# Interface.net
KiCad netlist of a schematic drawn in Altium Designer
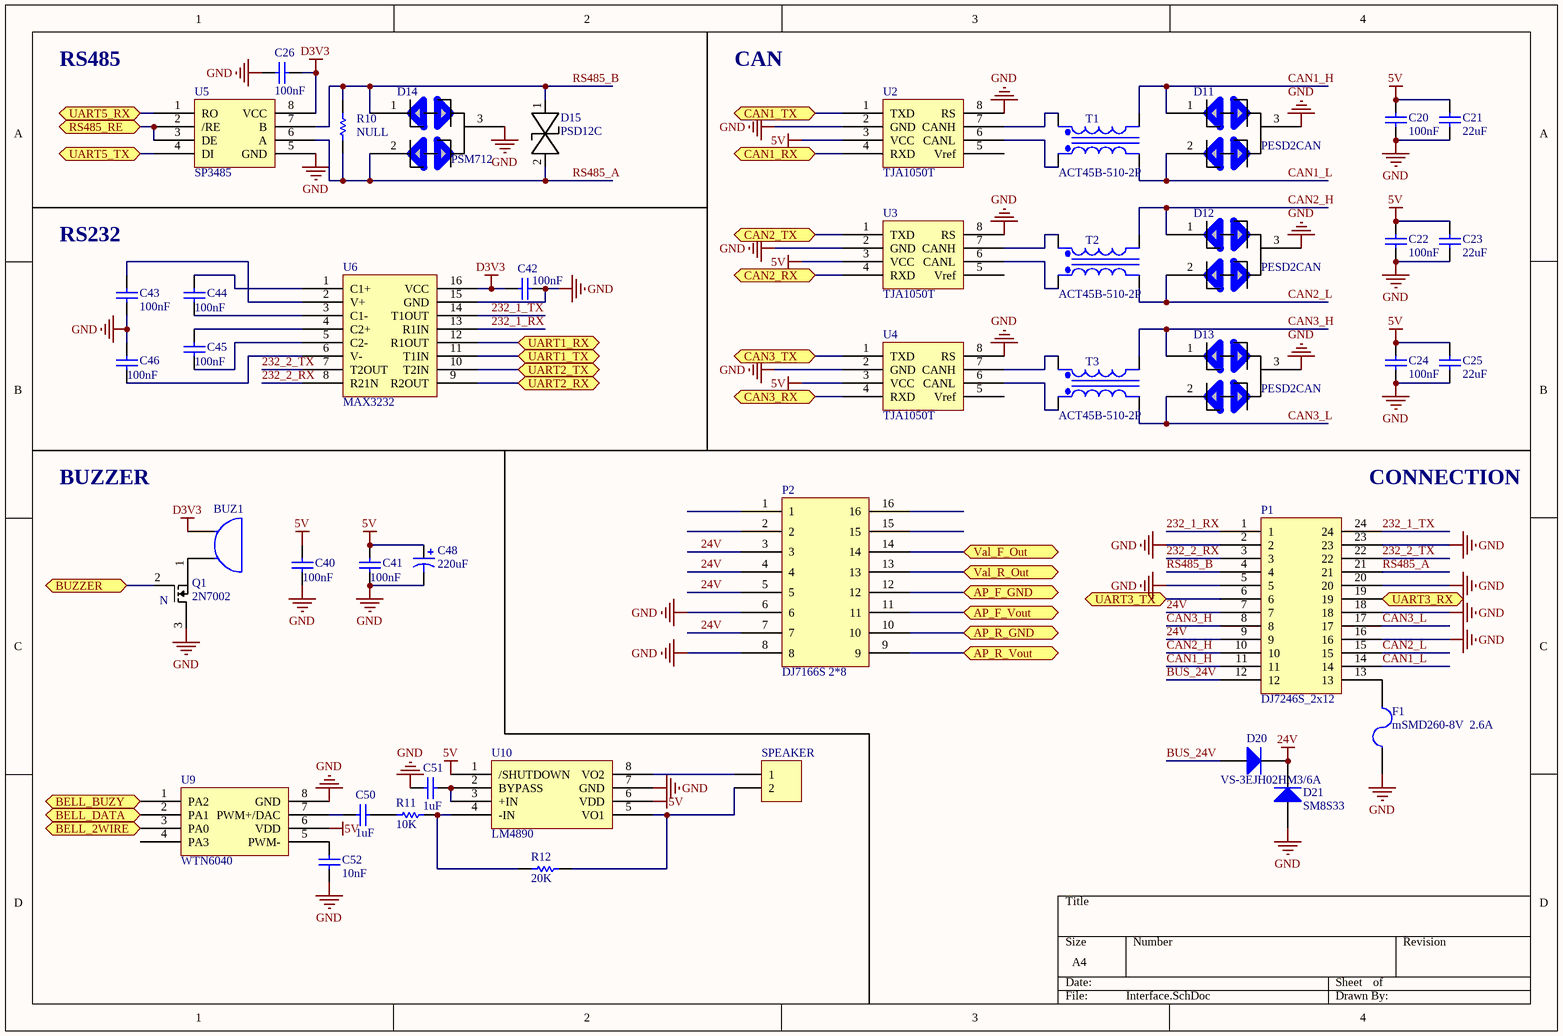
[diagram p0: Interface.SchDoc]

(export (version "E")
  (design (tool "Eeschema 10.0.6"))
  (components
    (comp (ref "BUZ1")
      (value "BUZZER")
      (footprint "BUZ0905")
      (description "Buzzer")
      (libsource (lib "杂元件库") (part "BUZZER"))
    )
    (comp (ref "C20")
      (value "100nF")
      (footprint "BinFeng:0402")
      (description "Capacitor")
      (fields (field (name "PUBLISHER") "Altium Limited"))
      (libsource (lib "Miscellaneous Devices") (part "Cap"))
    )
    (comp (ref "C21")
      (value "22uF")
      (footprint "0805")
      (description "Capacitor")
      (fields (field (name "PUBLISHER") "Altium Limited"))
      (libsource (lib "Miscellaneous Devices") (part "Cap"))
    )
    (comp (ref "C22")
      (value "100nF")
      (footprint "BinFeng:0402")
      (description "Capacitor")
      (fields (field (name "PUBLISHER") "Altium Limited"))
      (libsource (lib "Miscellaneous Devices") (part "Cap"))
    )
    (comp (ref "C23")
      (value "22uF")
      (footprint "0805")
      (description "Capacitor")
      (fields (field (name "PUBLISHER") "Altium Limited"))
      (libsource (lib "Miscellaneous Devices") (part "Cap"))
    )
    (comp (ref "C24")
      (value "100nF")
      (footprint "BinFeng:0402")
      (description "Capacitor")
      (fields (field (name "PUBLISHER") "Altium Limited"))
      (libsource (lib "Miscellaneous Devices") (part "Cap"))
    )
    (comp (ref "C25")
      (value "22uF")
      (footprint "0805")
      (description "Capacitor")
      (fields (field (name "PUBLISHER") "Altium Limited"))
      (libsource (lib "Miscellaneous Devices") (part "Cap"))
    )
    (comp (ref "C26")
      (value "100nF")
      (footprint "BinFeng:0603")
      (description "Capacitor")
      (fields (field (name "PUBLISHER") "Altium Limited"))
      (libsource (lib "Miscellaneous Devices") (part "Cap"))
    )
    (comp (ref "C40")
      (value "100nF")
      (footprint "BinFeng:0402")
      (description "Capacitor")
      (fields (field (name "PUBLISHER") "Altium Limited"))
      (libsource (lib "Miscellaneous Devices") (part "Cap"))
    )
    (comp (ref "C41")
      (value "100nF")
      (footprint "BinFeng:0402")
      (description "Capacitor")
      (fields (field (name "PUBLISHER") "Altium Limited"))
      (libsource (lib "Miscellaneous Devices") (part "Cap"))
    )
    (comp (ref "C42")
      (value "100nF")
      (footprint "BinFeng:0402")
      (description "Capacitor")
      (fields (field (name "PUBLISHER") "Altium Limited"))
      (libsource (lib "Miscellaneous Devices") (part "Cap"))
    )
    (comp (ref "C43")
      (value "100nF")
      (footprint "BinFeng:0402")
      (description "Capacitor")
      (fields (field (name "PUBLISHER") "Altium Limited"))
      (libsource (lib "Miscellaneous Devices") (part "Cap"))
    )
    (comp (ref "C44")
      (value "100nF")
      (footprint "BinFeng:0402")
      (description "Capacitor")
      (fields (field (name "PUBLISHER") "Altium Limited"))
      (libsource (lib "Miscellaneous Devices") (part "Cap"))
    )
    (comp (ref "C45")
      (value "100nF")
      (footprint "BinFeng:0402")
      (description "Capacitor")
      (fields (field (name "PUBLISHER") "Altium Limited"))
      (libsource (lib "Miscellaneous Devices") (part "Cap"))
    )
    (comp (ref "C46")
      (value "100nF")
      (footprint "BinFeng:0402")
      (description "Capacitor")
      (fields (field (name "PUBLISHER") "Altium Limited"))
      (libsource (lib "Miscellaneous Devices") (part "Cap"))
    )
    (comp (ref "C48")
      (value "220uF")
      (footprint "cap_pol_8*10.2")
      (description "Polarized Capacitor (Radial)")
      (fields (field (name "PUBLISHER") "Altium Limited"))
      (libsource (lib "Miscellaneous Devices") (part "Cap Pol1"))
    )
    (comp (ref "C50")
      (value "1uF")
      (footprint "BinFeng:0402")
      (description "Capacitor")
      (fields (field (name "PUBLISHER") "Altium Limited"))
      (libsource (lib "Miscellaneous Devices") (part "Cap"))
    )
    (comp (ref "C51")
      (value "1uF")
      (footprint "BinFeng:0402")
      (description "Capacitor")
      (fields (field (name "PUBLISHER") "Altium Limited"))
      (libsource (lib "Miscellaneous Devices") (part "Cap"))
    )
    (comp (ref "C52")
      (value "10nF")
      (footprint "BinFeng:0402")
      (description "Capacitor")
      (fields (field (name "PUBLISHER") "Altium Limited"))
      (libsource (lib "Miscellaneous Devices") (part "Cap"))
    )
    (comp (ref "D11")
      (value "PESD2CAN")
      (footprint "SOT23")
      (libsource (lib "BinFeng_Connectors") (part "PESD1CAN"))
    )
    (comp (ref "D12")
      (value "PESD2CAN")
      (footprint "SOT23")
      (libsource (lib "BinFeng_Connectors") (part "PESD1CAN"))
    )
    (comp (ref "D13")
      (value "PESD2CAN")
      (footprint "SOT23")
      (libsource (lib "BinFeng_Connectors") (part "PESD1CAN"))
    )
    (comp (ref "D14")
      (value "PSM712")
      (footprint "SOT23")
      (libsource (lib "BinFeng_Connectors") (part "PESD1CAN"))
    )
    (comp (ref "D15") (value "PSD12C") (footprint "SOD323") (libsource (lib "BinFeng_IC") (part "PSD12C")))
    (comp (ref "D20")
      (value "VS-3EJH02HM3/6A")
      (footprint "B290")
      (description "1 Amp General Purpose Rectifier")
      (fields (field (name "PUBLISHER") "Altium Limited"))
      (libsource (lib "Miscellaneous Devices") (part "Diode 1N4007"))
    )
    (comp (ref "D21")
      (value "SM8S33")
      (footprint "SM8S")
      (description "1 Amp General Purpose Rectifier")
      (fields (field (name "PUBLISHER") "Altium Limited"))
      (libsource (lib "Miscellaneous Devices") (part "Diode 1N4007"))
    )
    (comp (ref "F1")
      (value "mSMD260-8V  2.6A")
      (footprint "1812")
      (description "Fuse")
      (fields (field (name "PUBLISHER") "Altium Limited"))
      (libsource (lib "Miscellaneous Devices") (part "Fuse 2"))
    )
    (comp (ref "P1")
      (value "DJ7246S_2x12")
      (footprint "DJ7246S_2*12")
      (libsource (lib "BinFeng_IC") (part "DJ7246S-0.7-10AW"))
    )
    (comp (ref "P2")
      (value "DJ7166S 2*8")
      (footprint "hg:DJ7161S_0.7_10AW")
      (libsource (lib "hg") (part "DJ7166S"))
    )
    (comp (ref "Q1") (value "2N7002") (footprint "2N7002") (libsource (lib "seeder") (part "N-MOSFET")))
    (comp (ref "R10")
      (value "NULL")
      (footprint "BinFeng:0603")
      (description "Resistor")
      (fields (field (name "PUBLISHER") "Altium Limited"))
      (libsource (lib "Miscellaneous Devices") (part "Res1"))
    )
    (comp (ref "R11")
      (value "10K")
      (footprint "BinFeng:0402")
      (description "Resistor")
      (fields (field (name "PUBLISHER") "Altium Limited"))
      (libsource (lib "Miscellaneous Devices") (part "Res1"))
    )
    (comp (ref "R12")
      (value "20K")
      (footprint "BinFeng:0402")
      (description "Resistor")
      (fields (field (name "PUBLISHER") "Altium Limited"))
      (libsource (lib "Miscellaneous Devices") (part "Res1"))
    )
    (comp (ref "SPEAKER")
      (value "XH2.54-2PIN")
      (footprint "HDR1X2")
      (description "Header, 2-Pin")
      (fields (field (name "PUBLISHER") "Altium Limited"))
      (libsource (lib "Miscellaneous Connectors") (part "Header 2"))
    )
    (comp (ref "T1")
      (value "ACT45B-510-2P")
      (footprint "ACT45B-510-2P")
      (description "Transformer (Equivalent Circuit Model)")
      (fields (field (name "PUBLISHER") "Altium Limited"))
      (libsource (lib "Miscellaneous Devices") (part "Trans Eq"))
    )
    (comp (ref "T2")
      (value "ACT45B-510-2P")
      (footprint "ACT45B-510-2P")
      (description "Transformer (Equivalent Circuit Model)")
      (fields (field (name "PUBLISHER") "Altium Limited"))
      (libsource (lib "Miscellaneous Devices") (part "Trans Eq"))
    )
    (comp (ref "T3")
      (value "ACT45B-510-2P")
      (footprint "ACT45B-510-2P")
      (description "Transformer (Equivalent Circuit Model)")
      (fields (field (name "PUBLISHER") "Altium Limited"))
      (libsource (lib "Miscellaneous Devices") (part "Trans Eq"))
    )
    (comp (ref "U2")
      (value "TJA1050T")
      (footprint "SO8")
      (description "CAN Tranceiver")
      (libsource (lib "BinFeng_IC") (part "TJA1050T"))
    )
    (comp (ref "U3")
      (value "TJA1050T")
      (footprint "SO8")
      (description "CAN Tranceiver")
      (libsource (lib "BinFeng_IC") (part "TJA1050T"))
    )
    (comp (ref "U4")
      (value "TJA1050T")
      (footprint "SO8")
      (description "CAN Tranceiver")
      (libsource (lib "BinFeng_IC") (part "TJA1050T"))
    )
    (comp (ref "U5") (value "SP3485") (footprint "SO-8N") (libsource (lib "BinFeng_IC") (part "SP3485")))
    (comp (ref "U6") (value "MAX3232") (footprint "SO16") (libsource (lib "MAX3232") (part "MAX3232")))
    (comp (ref "U9") (value "WTN6040") (footprint "SO8") (libsource (lib "Schlib3") (part "WTN6040")))
    (comp (ref "U10") (value "LM4890") (footprint "MSOP8") (libsource (lib "BinFeng_IC") (part "LM4890")))
  )
  (nets
    (net (code "1") (name "/232_1_RX") (class "Default")
      (node (ref "P1") (pin "1") (pinfunction "1_1") (pintype "passive"))
      (node (ref "U6") (pin "13") (pinfunction "R1IN_13") (pintype "passive"))
    )
    (net (code "2") (name "/232_1_TX") (class "Default")
      (node (ref "P1") (pin "24") (pinfunction "24_24") (pintype "passive"))
      (node (ref "U6") (pin "14") (pinfunction "T1OUT_14") (pintype "passive"))
    )
    (net (code "3") (name "/232_2_RX") (class "Default")
      (node (ref "P1") (pin "3") (pinfunction "3_3") (pintype "passive"))
      (node (ref "U6") (pin "8") (pinfunction "R21N_8") (pintype "passive"))
    )
    (net (code "4") (name "/232_2_TX") (class "Default")
      (node (ref "P1") (pin "22") (pinfunction "22_22") (pintype "passive"))
      (node (ref "U6") (pin "7") (pinfunction "T2OUT_7") (pintype "passive"))
    )
    (net (code "5") (name "/AP_F_GND") (class "Default")
      (node (ref "P2") (pin "12") (pinfunction "12_12") (pintype "passive"))
    )
    (net (code "6") (name "/AP_F_Vout") (class "Default")
      (node (ref "P2") (pin "11") (pinfunction "11_11") (pintype "passive"))
    )
    (net (code "7") (name "/AP_R_GND") (class "Default")
      (node (ref "P2") (pin "10") (pinfunction "10_10") (pintype "passive"))
    )
    (net (code "8") (name "/AP_R_Vout") (class "Default")
      (node (ref "P2") (pin "9") (pinfunction "9_9") (pintype "passive"))
    )
    (net (code "9") (name "/BELL_2WIRE") (class "Default")
      (node (ref "U9") (pin "3") (pinfunction "PA0_3") (pintype "passive"))
    )
    (net (code "10") (name "/BELL_BUZY") (class "Default")
      (node (ref "U9") (pin "1") (pinfunction "PA2_1") (pintype "passive"))
    )
    (net (code "11") (name "/BELL_DATA") (class "Default")
      (node (ref "U9") (pin "2") (pinfunction "PA1_2") (pintype "passive"))
    )
    (net (code "12") (name "/BUS_24V") (class "Default")
      (node (ref "D20") (pin "1") (pinfunction "A_1") (pintype "passive"))
      (node (ref "P1") (pin "12") (pinfunction "12_12") (pintype "passive"))
    )
    (net (code "13") (name "/BUZZER") (class "Default")
      (node (ref "Q1") (pin "2") (pinfunction "G_2") (pintype "passive"))
    )
    (net (code "14") (name "/CAN1_H") (class "Default")
      (node (ref "D11") (pin "1") (pinfunction "11_1") (pintype "passive"))
      (node (ref "P1") (pin "11") (pinfunction "11_11") (pintype "passive"))
      (node (ref "T1") (pin "4") (pinfunction "Sec-_4") (pintype "passive"))
    )
    (net (code "15") (name "/CAN1_L") (class "Default")
      (node (ref "D11") (pin "2") (pinfunction "12_2") (pintype "passive"))
      (node (ref "P1") (pin "14") (pinfunction "14_14") (pintype "passive"))
      (node (ref "T1") (pin "2") (pinfunction "Pri-_2") (pintype "passive"))
    )
    (net (code "16") (name "/CAN1_RX") (class "Default")
      (node (ref "U2") (pin "4") (pinfunction "RXD_4") (pintype "passive"))
    )
    (net (code "17") (name "/CAN1_TX") (class "Default")
      (node (ref "U2") (pin "1") (pinfunction "TXD_1") (pintype "passive"))
    )
    (net (code "18") (name "/CAN2_H") (class "Default")
      (node (ref "D12") (pin "1") (pinfunction "11_1") (pintype "passive"))
      (node (ref "P1") (pin "10") (pinfunction "10_10") (pintype "passive"))
      (node (ref "T2") (pin "4") (pinfunction "Sec-_4") (pintype "passive"))
    )
    (net (code "19") (name "/CAN2_L") (class "Default")
      (node (ref "D12") (pin "2") (pinfunction "12_2") (pintype "passive"))
      (node (ref "P1") (pin "15") (pinfunction "15_15") (pintype "passive"))
      (node (ref "T2") (pin "2") (pinfunction "Pri-_2") (pintype "passive"))
    )
    (net (code "20") (name "/CAN2_RX") (class "Default")
      (node (ref "U3") (pin "4") (pinfunction "RXD_4") (pintype "passive"))
    )
    (net (code "21") (name "/CAN2_TX") (class "Default")
      (node (ref "U3") (pin "1") (pinfunction "TXD_1") (pintype "passive"))
    )
    (net (code "22") (name "/CAN3_H") (class "Default")
      (node (ref "D13") (pin "1") (pinfunction "11_1") (pintype "passive"))
      (node (ref "P1") (pin "8") (pinfunction "8_8") (pintype "passive"))
      (node (ref "T3") (pin "4") (pinfunction "Sec-_4") (pintype "passive"))
    )
    (net (code "23") (name "/CAN3_L") (class "Default")
      (node (ref "D13") (pin "2") (pinfunction "12_2") (pintype "passive"))
      (node (ref "P1") (pin "17") (pinfunction "17_17") (pintype "passive"))
      (node (ref "T3") (pin "2") (pinfunction "Pri-_2") (pintype "passive"))
    )
    (net (code "24") (name "/CAN3_RX") (class "Default")
      (node (ref "U4") (pin "4") (pinfunction "RXD_4") (pintype "passive"))
    )
    (net (code "25") (name "/CAN3_TX") (class "Default")
      (node (ref "U4") (pin "1") (pinfunction "TXD_1") (pintype "passive"))
    )
    (net (code "26") (name "/RS485_A") (class "Default")
      (node (ref "D14") (pin "2") (pinfunction "12_2") (pintype "passive"))
      (node (ref "D15") (pin "2") (pinfunction "2_2") (pintype "passive"))
      (node (ref "P1") (pin "21") (pinfunction "21_21") (pintype "passive"))
      (node (ref "R10") (pin "2") (pinfunction "2_2") (pintype "passive"))
      (node (ref "U5") (pin "6") (pinfunction "A_6") (pintype "passive"))
    )
    (net (code "27") (name "/RS485_B") (class "Default")
      (node (ref "D14") (pin "1") (pinfunction "11_1") (pintype "passive"))
      (node (ref "D15") (pin "1") (pinfunction "1_1") (pintype "passive"))
      (node (ref "P1") (pin "4") (pinfunction "4_4") (pintype "passive"))
      (node (ref "R10") (pin "1") (pinfunction "1_1") (pintype "passive"))
      (node (ref "U5") (pin "7") (pinfunction "B_7") (pintype "passive"))
    )
    (net (code "28") (name "/RS485_RE") (class "Default")
      (node (ref "U5") (pin "2") (pinfunction "/RE_2") (pintype "passive"))
      (node (ref "U5") (pin "3") (pinfunction "DE_3") (pintype "passive"))
    )
    (net (code "29") (name "/UART1_RX") (class "Default")
      (node (ref "U6") (pin "12") (pinfunction "R1OUT_12") (pintype "passive"))
    )
    (net (code "30") (name "/UART1_TX") (class "Default")
      (node (ref "U6") (pin "11") (pinfunction "T1IN_11") (pintype "passive"))
    )
    (net (code "31") (name "/UART2_RX") (class "Default")
      (node (ref "U6") (pin "9") (pinfunction "R2OUT_9") (pintype "passive"))
    )
    (net (code "32") (name "/UART2_TX") (class "Default")
      (node (ref "U6") (pin "10") (pinfunction "T2IN_10") (pintype "passive"))
    )
    (net (code "33") (name "/UART3_RX") (class "Default")
      (node (ref "P1") (pin "19") (pinfunction "19_19") (pintype "passive"))
    )
    (net (code "34") (name "/UART3_TX") (class "Default")
      (node (ref "P1") (pin "6") (pinfunction "6_6") (pintype "passive"))
    )
    (net (code "35") (name "/UART5_RX") (class "Default")
      (node (ref "U5") (pin "1") (pinfunction "RO_1") (pintype "passive"))
    )
    (net (code "36") (name "/UART5_TX") (class "Default")
      (node (ref "U5") (pin "4") (pinfunction "DI_4") (pintype "passive"))
    )
    (net (code "37") (name "/Val_F_Out") (class "Default")
      (node (ref "P2") (pin "14") (pinfunction "14_14") (pintype "passive"))
    )
    (net (code "38") (name "/Val_R_Out") (class "Default")
      (node (ref "P2") (pin "13") (pinfunction "13_13") (pintype "passive"))
    )
    (net (code "39") (name "5V") (class "Default")
      (node (ref "C20") (pin "2") (pinfunction "2_2") (pintype "passive"))
      (node (ref "C21") (pin "2") (pinfunction "2_2") (pintype "passive"))
      (node (ref "C22") (pin "2") (pinfunction "2_2") (pintype "passive"))
      (node (ref "C23") (pin "2") (pinfunction "2_2") (pintype "passive"))
      (node (ref "C24") (pin "2") (pinfunction "2_2") (pintype "passive"))
      (node (ref "C25") (pin "2") (pinfunction "2_2") (pintype "passive"))
      (node (ref "C40") (pin "2") (pinfunction "2_2") (pintype "passive"))
      (node (ref "C41") (pin "2") (pinfunction "2_2") (pintype "passive"))
      (node (ref "C48") (pin "1") (pinfunction "1_1") (pintype "passive"))
      (node (ref "U10") (pin "1") (pinfunction "/SHUTDOWN_1") (pintype "passive"))
      (node (ref "U10") (pin "6") (pinfunction "VDD_6") (pintype "passive"))
      (node (ref "U2") (pin "3") (pinfunction "VCC_3") (pintype "passive"))
      (node (ref "U3") (pin "3") (pinfunction "VCC_3") (pintype "passive"))
      (node (ref "U4") (pin "3") (pinfunction "VCC_3") (pintype "passive"))
      (node (ref "U9") (pin "6") (pinfunction "VDD_6") (pintype "power_in"))
    )
    (net (code "40") (name "24V") (class "Default")
      (node (ref "D20") (pin "2") (pinfunction "K_2") (pintype "passive"))
      (node (ref "D21") (pin "2") (pinfunction "K_2") (pintype "passive"))
      (node (ref "P1") (pin "7") (pinfunction "7_7") (pintype "passive"))
      (node (ref "P1") (pin "9") (pinfunction "9_9") (pintype "passive"))
      (node (ref "P2") (pin "3") (pinfunction "3_3") (pintype "passive"))
      (node (ref "P2") (pin "4") (pinfunction "4_4") (pintype "passive"))
      (node (ref "P2") (pin "5") (pinfunction "5_5") (pintype "passive"))
      (node (ref "P2") (pin "7") (pinfunction "7_7") (pintype "passive"))
    )
    (net (code "41") (name "D3V3") (class "Default")
      (node (ref "BUZ1") (pin "1") (pinfunction "A_1") (pintype "passive"))
      (node (ref "C26") (pin "2") (pinfunction "2_2") (pintype "passive"))
      (node (ref "C42") (pin "2") (pinfunction "2_2") (pintype "passive"))
      (node (ref "U5") (pin "8") (pinfunction "VCC_8") (pintype "passive"))
      (node (ref "U6") (pin "16") (pinfunction "VCC_16") (pintype "passive"))
    )
    (net (code "42") (name "GND") (class "Default")
      (node (ref "C20") (pin "1") (pinfunction "1_1") (pintype "passive"))
      (node (ref "C21") (pin "1") (pinfunction "1_1") (pintype "passive"))
      (node (ref "C22") (pin "1") (pinfunction "1_1") (pintype "passive"))
      (node (ref "C23") (pin "1") (pinfunction "1_1") (pintype "passive"))
      (node (ref "C24") (pin "1") (pinfunction "1_1") (pintype "passive"))
      (node (ref "C25") (pin "1") (pinfunction "1_1") (pintype "passive"))
      (node (ref "C26") (pin "1") (pinfunction "1_1") (pintype "passive"))
      (node (ref "C40") (pin "1") (pinfunction "1_1") (pintype "passive"))
      (node (ref "C41") (pin "1") (pinfunction "1_1") (pintype "passive"))
      (node (ref "C42") (pin "1") (pinfunction "1_1") (pintype "passive"))
      (node (ref "C43") (pin "2") (pinfunction "2_2") (pintype "passive"))
      (node (ref "C46") (pin "2") (pinfunction "2_2") (pintype "passive"))
      (node (ref "C48") (pin "2") (pinfunction "2_2") (pintype "passive"))
      (node (ref "C51") (pin "2") (pinfunction "2_2") (pintype "passive"))
      (node (ref "C52") (pin "2") (pinfunction "2_2") (pintype "passive"))
      (node (ref "D11") (pin "3") (pinfunction "13_3") (pintype "passive"))
      (node (ref "D12") (pin "3") (pinfunction "13_3") (pintype "passive"))
      (node (ref "D13") (pin "3") (pinfunction "13_3") (pintype "passive"))
      (node (ref "D14") (pin "3") (pinfunction "13_3") (pintype "passive"))
      (node (ref "D21") (pin "1") (pinfunction "A_1") (pintype "passive"))
      (node (ref "F1") (pin "2") (pinfunction "2_2") (pintype "passive"))
      (node (ref "P1") (pin "16") (pinfunction "16_16") (pintype "passive"))
      (node (ref "P1") (pin "18") (pinfunction "18_18") (pintype "passive"))
      (node (ref "P1") (pin "2") (pinfunction "2_2") (pintype "passive"))
      (node (ref "P1") (pin "20") (pinfunction "20_20") (pintype "passive"))
      (node (ref "P1") (pin "23") (pinfunction "23_23") (pintype "passive"))
      (node (ref "P1") (pin "5") (pinfunction "5_5") (pintype "passive"))
      (node (ref "P2") (pin "6") (pinfunction "6_6") (pintype "passive"))
      (node (ref "P2") (pin "8") (pinfunction "8_8") (pintype "passive"))
      (node (ref "Q1") (pin "3") (pinfunction "S_3") (pintype "passive"))
      (node (ref "U10") (pin "7") (pinfunction "GND_7") (pintype "passive"))
      (node (ref "U2") (pin "2") (pinfunction "GND_2") (pintype "passive"))
      (node (ref "U2") (pin "8") (pinfunction "RS_8") (pintype "passive"))
      (node (ref "U3") (pin "2") (pinfunction "GND_2") (pintype "passive"))
      (node (ref "U3") (pin "8") (pinfunction "RS_8") (pintype "passive"))
      (node (ref "U4") (pin "2") (pinfunction "GND_2") (pintype "passive"))
      (node (ref "U4") (pin "8") (pinfunction "RS_8") (pintype "passive"))
      (node (ref "U5") (pin "5") (pinfunction "GND_5") (pintype "passive"))
      (node (ref "U6") (pin "15") (pinfunction "GND_15") (pintype "passive"))
      (node (ref "U9") (pin "8") (pinfunction "GND_8") (pintype "power_in"))
    )
    (net (code "43") (name "Net-(BUZ1-B)") (class "Default")
      (node (ref "BUZ1") (pin "2") (pinfunction "B_2") (pintype "passive"))
      (node (ref "Q1") (pin "1") (pinfunction "D_1") (pintype "passive"))
    )
    (net (code "44") (name "Net-(C50-Pad1)") (class "Default")
      (node (ref "C50") (pin "1") (pinfunction "1_1") (pintype "passive"))
      (node (ref "R11") (pin "1") (pinfunction "1_1") (pintype "passive"))
    )
    (net (code "45") (name "Net-(F1-Pad1)") (class "Default")
      (node (ref "F1") (pin "1") (pinfunction "1_1") (pintype "passive"))
      (node (ref "P1") (pin "13") (pinfunction "13_13") (pintype "passive"))
    )
    (net (code "46") (name "Net-(T1-Pri+)") (class "Default")
      (node (ref "T1") (pin "1") (pinfunction "Pri+_1") (pintype "passive"))
      (node (ref "U2") (pin "6") (pinfunction "CANL_6") (pintype "passive"))
    )
    (net (code "47") (name "Net-(T1-Sec+)") (class "Default")
      (node (ref "T1") (pin "3") (pinfunction "Sec+_3") (pintype "passive"))
      (node (ref "U2") (pin "7") (pinfunction "CANH_7") (pintype "passive"))
    )
    (net (code "48") (name "Net-(T2-Pri+)") (class "Default")
      (node (ref "T2") (pin "1") (pinfunction "Pri+_1") (pintype "passive"))
      (node (ref "U3") (pin "6") (pinfunction "CANL_6") (pintype "passive"))
    )
    (net (code "49") (name "Net-(T2-Sec+)") (class "Default")
      (node (ref "T2") (pin "3") (pinfunction "Sec+_3") (pintype "passive"))
      (node (ref "U3") (pin "7") (pinfunction "CANH_7") (pintype "passive"))
    )
    (net (code "50") (name "Net-(T3-Pri+)") (class "Default")
      (node (ref "T3") (pin "1") (pinfunction "Pri+_1") (pintype "passive"))
      (node (ref "U4") (pin "6") (pinfunction "CANL_6") (pintype "passive"))
    )
    (net (code "51") (name "Net-(T3-Sec+)") (class "Default")
      (node (ref "T3") (pin "3") (pinfunction "Sec+_3") (pintype "passive"))
      (node (ref "U4") (pin "7") (pinfunction "CANH_7") (pintype "passive"))
    )
    (net (code "52") (name "Net-(U6-C1+)") (class "Default")
      (node (ref "C44") (pin "2") (pinfunction "2_2") (pintype "passive"))
      (node (ref "U6") (pin "1") (pinfunction "C1+_1") (pintype "passive"))
    )
    (net (code "53") (name "Net-(U6-C1-)") (class "Default")
      (node (ref "C44") (pin "1") (pinfunction "1_1") (pintype "passive"))
      (node (ref "U6") (pin "3") (pinfunction "C1-_3") (pintype "passive"))
    )
    (net (code "54") (name "Net-(U6-C2+)") (class "Default")
      (node (ref "C45") (pin "2") (pinfunction "2_2") (pintype "passive"))
      (node (ref "U6") (pin "4") (pinfunction "C2+_4") (pintype "passive"))
    )
    (net (code "55") (name "Net-(U6-C2-)") (class "Default")
      (node (ref "C45") (pin "1") (pinfunction "1_1") (pintype "passive"))
      (node (ref "U6") (pin "5") (pinfunction "C2-_5") (pintype "passive"))
    )
    (net (code "56") (name "Net-(U6-V+)") (class "Default")
      (node (ref "C43") (pin "1") (pinfunction "1_1") (pintype "passive"))
      (node (ref "U6") (pin "2") (pinfunction "V+_2") (pintype "passive"))
    )
    (net (code "57") (name "Net-(U6-V-)") (class "Default")
      (node (ref "C46") (pin "1") (pinfunction "1_1") (pintype "passive"))
      (node (ref "U6") (pin "6") (pinfunction "V-_6") (pintype "passive"))
    )
    (net (code "58") (name "Net-(U9-PWM+{slash}DAC)") (class "Default")
      (node (ref "C50") (pin "2") (pinfunction "2_2") (pintype "passive"))
      (node (ref "U9") (pin "7") (pinfunction "PWM+/DAC_7") (pintype "passive"))
    )
    (net (code "59") (name "Net-(U9-PWM-)") (class "Default")
      (node (ref "C52") (pin "1") (pinfunction "1_1") (pintype "passive"))
      (node (ref "U9") (pin "5") (pinfunction "PWM-_5") (pintype "passive"))
    )
    (net (code "60") (name "Net-(U10-+IN)") (class "Default")
      (node (ref "C51") (pin "1") (pinfunction "1_1") (pintype "passive"))
      (node (ref "U10") (pin "2") (pinfunction "BYPASS_2") (pintype "passive"))
      (node (ref "U10") (pin "3") (pinfunction "+IN_3") (pintype "passive"))
    )
    (net (code "61") (name "Net-(U10--IN)") (class "Default")
      (node (ref "R11") (pin "2") (pinfunction "2_2") (pintype "passive"))
      (node (ref "R12") (pin "1") (pinfunction "1_1") (pintype "passive"))
      (node (ref "U10") (pin "4") (pinfunction "-IN_4") (pintype "passive"))
    )
    (net (code "62") (name "Net-(U10-VO1)") (class "Default")
      (node (ref "R12") (pin "2") (pinfunction "2_2") (pintype "passive"))
      (node (ref "SPEAKER") (pin "2") (pinfunction "2_2") (pintype "passive"))
      (node (ref "U10") (pin "5") (pinfunction "VO1_5") (pintype "passive"))
    )
    (net (code "63") (name "Net-(U10-VO2)") (class "Default")
      (node (ref "SPEAKER") (pin "1") (pinfunction "1_1") (pintype "passive"))
      (node (ref "U10") (pin "8") (pinfunction "VO2_8") (pintype "passive"))
    )
    (net (code "64") (name "unconnected-(P2-Pad1)") (class "Default")
      (node (ref "P2") (pin "1") (pinfunction "1_1") (pintype "passive"))
    )
    (net (code "65") (name "unconnected-(P2-Pad2)") (class "Default")
      (node (ref "P2") (pin "2") (pinfunction "2_2") (pintype "passive"))
    )
    (net (code "66") (name "unconnected-(P2-Pad15)") (class "Default")
      (node (ref "P2") (pin "15") (pinfunction "15_15") (pintype "passive"))
    )
    (net (code "67") (name "unconnected-(P2-Pad16)") (class "Default")
      (node (ref "P2") (pin "16") (pinfunction "16_16") (pintype "passive"))
    )
    (net (code "68") (name "unconnected-(U2-Vref-Pad5)") (class "Default")
      (node (ref "U2") (pin "5") (pinfunction "Vref_5") (pintype "passive"))
    )
    (net (code "69") (name "unconnected-(U3-Vref-Pad5)") (class "Default")
      (node (ref "U3") (pin "5") (pinfunction "Vref_5") (pintype "passive"))
    )
    (net (code "70") (name "unconnected-(U4-Vref-Pad5)") (class "Default")
      (node (ref "U4") (pin "5") (pinfunction "Vref_5") (pintype "passive"))
    )
    (net (code "71") (name "unconnected-(U9-PA3-Pad4)") (class "Default")
      (node (ref "U9") (pin "4") (pinfunction "PA3_4") (pintype "passive"))
    )
  )
)
